# RNS_1board.net
KiCad netlist of a schematic drawn in EAGLE
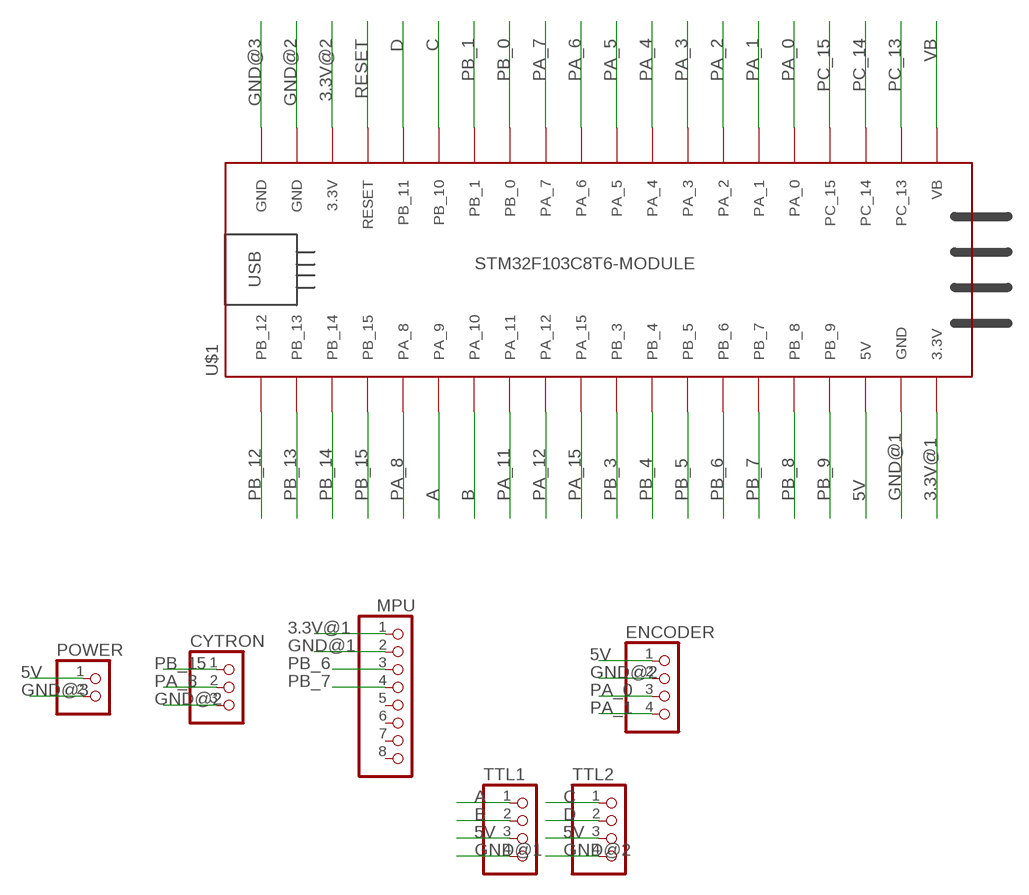
[diagram p0: schematic, sheet 1]

(export (version "E")
  (design (tool "Eeschema 10.0.6"))
  (components
    (comp (ref "CYTRON")
      (value "PINHD-3_DATA")
      (footprint "eagle-import:1X03_DATA")
      (libsource (lib "eagle-import") (part "PINHD-3_DATA"))
    )
    (comp (ref "ENCODER")
      (value "PINHD-4_DATA")
      (footprint "eagle-import:1X04_DATA")
      (libsource (lib "eagle-import") (part "PINHD-4_DATA"))
    )
    (comp (ref "MPU")
      (value "PINHD-8_DATA")
      (footprint "eagle-import:1X08_DATA")
      (libsource (lib "eagle-import") (part "PINHD-8_DATA"))
    )
    (comp (ref "POWER")
      (value "PINHD-2_DATA")
      (footprint "eagle-import:1X02_DATA")
      (libsource (lib "eagle-import") (part "PINHD-2_DATA"))
    )
    (comp (ref "TTL1")
      (value "PINHD-4_DATA")
      (footprint "eagle-import:1X04_DATA")
      (libsource (lib "eagle-import") (part "PINHD-4_DATA"))
    )
    (comp (ref "TTL2")
      (value "PINHD-4_DATA")
      (footprint "eagle-import:1X04_DATA")
      (libsource (lib "eagle-import") (part "PINHD-4_DATA"))
    )
    (comp (ref "U$1")
      (value "STM32F103C8T6-MODULE")
      (footprint "eagle-import:STM32F103C8T6-MODULE")
      (libsource (lib "eagle-import") (part "STM32F103C8T6-MODULE"))
    )
  )
  (nets
    (net (code "1") (name "/3.3V@1") (class "Default")
      (node (ref "MPU") (pin "1") (pinfunction "1_1") (pintype "passive"))
      (node (ref "U$1") (pin "3.3V_1") (pinfunction "3.3V_3.3V_1") (pintype "bidirectional"))
    )
    (net (code "2") (name "/3.3V@2") (class "Default")
      (node (ref "U$1") (pin "3.3V_2") (pinfunction "3.3V_3.3V_2") (pintype "bidirectional"))
    )
    (net (code "3") (name "/5V") (class "Default")
      (node (ref "ENCODER") (pin "1") (pinfunction "1_1") (pintype "passive"))
      (node (ref "POWER") (pin "1") (pinfunction "1_1") (pintype "passive"))
      (node (ref "TTL1") (pin "3") (pinfunction "3_3") (pintype "passive"))
      (node (ref "TTL2") (pin "3") (pinfunction "3_3") (pintype "passive"))
      (node (ref "U$1") (pin "5V") (pinfunction "5V_5V") (pintype "bidirectional"))
    )
    (net (code "4") (name "/A") (class "Default")
      (node (ref "TTL1") (pin "1") (pinfunction "1_1") (pintype "passive"))
      (node (ref "U$1") (pin "PA_9") (pinfunction "PA_9_PA_9") (pintype "bidirectional"))
    )
    (net (code "5") (name "/B") (class "Default")
      (node (ref "TTL1") (pin "2") (pinfunction "2_2") (pintype "passive"))
      (node (ref "U$1") (pin "PA_10") (pinfunction "PA_10_PA_10") (pintype "bidirectional"))
    )
    (net (code "6") (name "/C") (class "Default")
      (node (ref "TTL2") (pin "1") (pinfunction "1_1") (pintype "passive"))
      (node (ref "U$1") (pin "PB_10") (pinfunction "PB_10_PB_10") (pintype "bidirectional"))
    )
    (net (code "7") (name "/D") (class "Default")
      (node (ref "TTL2") (pin "2") (pinfunction "2_2") (pintype "passive"))
      (node (ref "U$1") (pin "PB_11") (pinfunction "PB_11_PB_11") (pintype "bidirectional"))
    )
    (net (code "8") (name "/GND@1") (class "Default")
      (node (ref "MPU") (pin "2") (pinfunction "2_2") (pintype "passive"))
      (node (ref "TTL1") (pin "4") (pinfunction "4_4") (pintype "passive"))
      (node (ref "U$1") (pin "GND_1") (pinfunction "GND_GND_1") (pintype "bidirectional"))
    )
    (net (code "9") (name "/GND@2") (class "Default")
      (node (ref "CYTRON") (pin "3") (pinfunction "3_3") (pintype "passive"))
      (node (ref "ENCODER") (pin "2") (pinfunction "2_2") (pintype "passive"))
      (node (ref "TTL2") (pin "4") (pinfunction "4_4") (pintype "passive"))
      (node (ref "U$1") (pin "GND_2") (pinfunction "GND_GND_2") (pintype "bidirectional"))
    )
    (net (code "10") (name "/GND@3") (class "Default")
      (node (ref "POWER") (pin "2") (pinfunction "2_2") (pintype "passive"))
      (node (ref "U$1") (pin "GND_3") (pinfunction "GND_GND_3") (pintype "power_in"))
    )
    (net (code "11") (name "/PA_0") (class "Default")
      (node (ref "ENCODER") (pin "3") (pinfunction "3_3") (pintype "passive"))
      (node (ref "U$1") (pin "PA_0") (pinfunction "PA_0_PA_0") (pintype "bidirectional"))
    )
    (net (code "12") (name "/PA_1") (class "Default")
      (node (ref "ENCODER") (pin "4") (pinfunction "4_4") (pintype "passive"))
      (node (ref "U$1") (pin "PA_1") (pinfunction "PA_1_PA_1") (pintype "bidirectional"))
    )
    (net (code "13") (name "/PA_2") (class "Default")
      (node (ref "U$1") (pin "PA_2") (pinfunction "PA_2_PA_2") (pintype "bidirectional"))
    )
    (net (code "14") (name "/PA_3") (class "Default")
      (node (ref "U$1") (pin "PA_3") (pinfunction "PA_3_PA_3") (pintype "bidirectional"))
    )
    (net (code "15") (name "/PA_4") (class "Default")
      (node (ref "U$1") (pin "PA_4") (pinfunction "PA_4_PA_4") (pintype "bidirectional"))
    )
    (net (code "16") (name "/PA_5") (class "Default")
      (node (ref "U$1") (pin "PA_5") (pinfunction "PA_5_PA_5") (pintype "bidirectional"))
    )
    (net (code "17") (name "/PA_6") (class "Default")
      (node (ref "U$1") (pin "PA_6") (pinfunction "PA_6_PA_6") (pintype "bidirectional"))
    )
    (net (code "18") (name "/PA_7") (class "Default")
      (node (ref "U$1") (pin "PA_7") (pinfunction "PA_7_PA_7") (pintype "bidirectional"))
    )
    (net (code "19") (name "/PA_8") (class "Default")
      (node (ref "CYTRON") (pin "2") (pinfunction "2_2") (pintype "passive"))
      (node (ref "U$1") (pin "PA_8") (pinfunction "PA_8_PA_8") (pintype "bidirectional"))
    )
    (net (code "20") (name "/PA_11") (class "Default")
      (node (ref "U$1") (pin "PA_11") (pinfunction "PA_11_PA_11") (pintype "bidirectional"))
    )
    (net (code "21") (name "/PA_12") (class "Default")
      (node (ref "U$1") (pin "PA_12") (pinfunction "PA_12_PA_12") (pintype "bidirectional"))
    )
    (net (code "22") (name "/PA_15") (class "Default")
      (node (ref "U$1") (pin "PA_15") (pinfunction "PA_15_PA_15") (pintype "bidirectional"))
    )
    (net (code "23") (name "/PB_0") (class "Default")
      (node (ref "U$1") (pin "PB_0") (pinfunction "PB_0_PB_0") (pintype "bidirectional"))
    )
    (net (code "24") (name "/PB_1") (class "Default")
      (node (ref "U$1") (pin "PB_1") (pinfunction "PB_1_PB_1") (pintype "bidirectional"))
    )
    (net (code "25") (name "/PB_3") (class "Default")
      (node (ref "U$1") (pin "PB_3") (pinfunction "PB_3_PB_3") (pintype "bidirectional"))
    )
    (net (code "26") (name "/PB_4") (class "Default")
      (node (ref "U$1") (pin "PB_4") (pinfunction "PB_4_PB_4") (pintype "bidirectional"))
    )
    (net (code "27") (name "/PB_5") (class "Default")
      (node (ref "U$1") (pin "PB_5") (pinfunction "PB_5_PB_5") (pintype "bidirectional"))
    )
    (net (code "28") (name "/PB_6") (class "Default")
      (node (ref "MPU") (pin "3") (pinfunction "3_3") (pintype "passive"))
      (node (ref "U$1") (pin "PB_6") (pinfunction "PB_6_PB_6") (pintype "bidirectional"))
    )
    (net (code "29") (name "/PB_7") (class "Default")
      (node (ref "MPU") (pin "4") (pinfunction "4_4") (pintype "passive"))
      (node (ref "U$1") (pin "PB_7") (pinfunction "PB_7_PB_7") (pintype "bidirectional"))
    )
    (net (code "30") (name "/PB_8") (class "Default")
      (node (ref "U$1") (pin "PB_8") (pinfunction "PB_8_PB_8") (pintype "bidirectional"))
    )
    (net (code "31") (name "/PB_9") (class "Default")
      (node (ref "U$1") (pin "PB_9") (pinfunction "PB_9_PB_9") (pintype "bidirectional"))
    )
    (net (code "32") (name "/PB_12") (class "Default")
      (node (ref "U$1") (pin "PB_12") (pinfunction "PB_12_PB_12") (pintype "bidirectional"))
    )
    (net (code "33") (name "/PB_13") (class "Default")
      (node (ref "U$1") (pin "PB_13") (pinfunction "PB_13_PB_13") (pintype "bidirectional"))
    )
    (net (code "34") (name "/PB_14") (class "Default")
      (node (ref "U$1") (pin "PB_14") (pinfunction "PB_14_PB_14") (pintype "bidirectional"))
    )
    (net (code "35") (name "/PB_15") (class "Default")
      (node (ref "CYTRON") (pin "1") (pinfunction "1_1") (pintype "passive"))
      (node (ref "U$1") (pin "PB_15") (pinfunction "PB_15_PB_15") (pintype "bidirectional"))
    )
    (net (code "36") (name "/PC_13") (class "Default")
      (node (ref "U$1") (pin "PC_13") (pinfunction "PC_13_PC_13") (pintype "bidirectional"))
    )
    (net (code "37") (name "/PC_14") (class "Default")
      (node (ref "U$1") (pin "PC_14") (pinfunction "PC_14_PC_14") (pintype "bidirectional"))
    )
    (net (code "38") (name "/PC_15") (class "Default")
      (node (ref "U$1") (pin "PC_15") (pinfunction "PC_15_PC_15") (pintype "bidirectional"))
    )
    (net (code "39") (name "/RESET") (class "Default")
      (node (ref "U$1") (pin "RESET") (pinfunction "RESET_RESET") (pintype "bidirectional"))
    )
    (net (code "40") (name "/VB") (class "Default")
      (node (ref "U$1") (pin "VB") (pinfunction "VB_VB") (pintype "bidirectional"))
    )
    (net (code "41") (name "unconnected-(MPU-Pad5)") (class "Default")
      (node (ref "MPU") (pin "5") (pinfunction "5_5") (pintype "passive"))
    )
    (net (code "42") (name "unconnected-(MPU-Pad6)") (class "Default")
      (node (ref "MPU") (pin "6") (pinfunction "6_6") (pintype "passive"))
    )
    (net (code "43") (name "unconnected-(MPU-Pad7)") (class "Default")
      (node (ref "MPU") (pin "7") (pinfunction "7_7") (pintype "passive"))
    )
    (net (code "44") (name "unconnected-(MPU-Pad8)") (class "Default")
      (node (ref "MPU") (pin "8") (pinfunction "8_8") (pintype "passive"))
    )
  )
)
